# SensorPower.net
KiCad netlist of a schematic drawn in Altium Designer
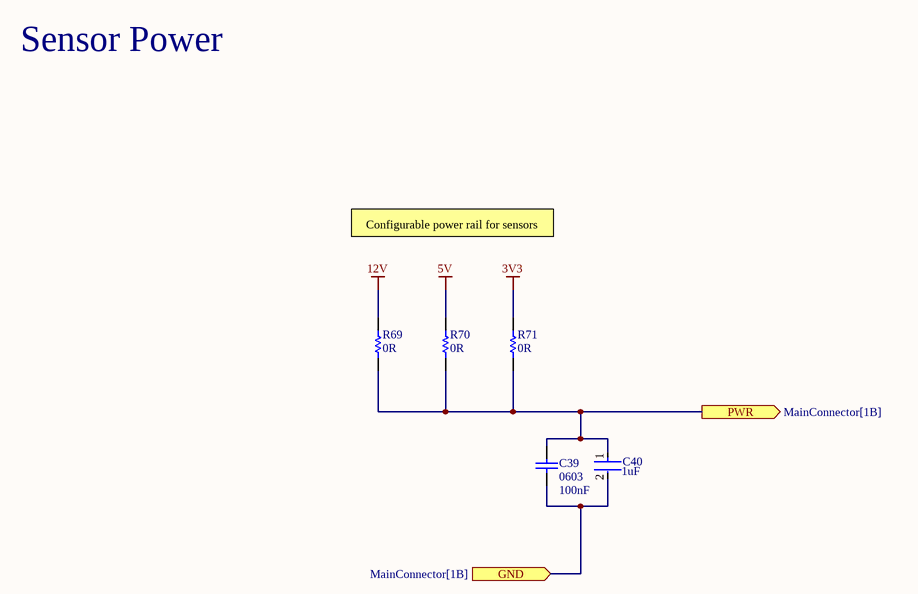
[diagram p0: SensorPower.SchDoc]

(export (version "E")
  (design (tool "Eeschema 10.0.6"))
  (components
    (comp (ref "C39")
      (value "C0603X104K5RACTU")
      (footprint "CAPC1608X87X35NL15T15")
      (fields
        (field (name "MANUFACTURER") "Kemet")
        (field (name "CASE CODE (IMPERIAL)") "0603")
        (field (name "CAPACITANCE") "100nF")
        (field (name "TOLERANCE") "10%")
        (field (name "VOLTAGE") "50V")
      )
      (libsource (lib "Altium Content Vault") (part "CAP"))
    )
    (comp (ref "C40")
      (value "CL10A105KA8NNNC")
      (footprint "FP-CL10-IPC_C")
      (description "Cap Ceramic 1uF 25V X5R ±10% Pad SMD 0603 +85°C T/R")
      (fields
        (field (name "CAPACITANCE") "1uF")
        (field (name "VOLTAGE") "25V")
        (field (name "TOLERANCE") "10%")
      )
      (libsource (lib "Altium Content Vault") (part "b4654b650e69147ec39a6b967a45e02"))
    )
    (comp (ref "R69")
      (value "RC0805JR-100RL")
      (footprint "RESC2013X60X35LL10T20")
      (description "Chip Resistor, 0 Ohm, +/- 5%, 125 mW, -55 to 155 degC, 0805 (2012 Metric), RoHS, Tape and Reel")
      (fields (field (name "MANUFACTURER") "Yageo") (field (name "RESISTANCE") "0R"))
      (libsource (lib "Altium Content Vault") (part "RES-2"))
    )
    (comp (ref "R70")
      (value "RC0805JR-100RL")
      (footprint "RESC2013X60X35LL10T20")
      (description "Chip Resistor, 0 Ohm, +/- 5%, 125 mW, -55 to 155 degC, 0805 (2012 Metric), RoHS, Tape and Reel")
      (fields (field (name "MANUFACTURER") "Yageo") (field (name "RESISTANCE") "0R"))
      (libsource (lib "Altium Content Vault") (part "RES-2"))
    )
    (comp (ref "R71")
      (value "RC0805JR-100RL")
      (footprint "RESC2013X60X35LL10T20")
      (description "Chip Resistor, 0 Ohm, +/- 5%, 125 mW, -55 to 155 degC, 0805 (2012 Metric), RoHS, Tape and Reel")
      (fields (field (name "MANUFACTURER") "Yageo") (field (name "RESISTANCE") "0R"))
      (libsource (lib "Altium Content Vault") (part "RES-2"))
    )
  )
  (nets
    (net (code "1") (name "/GND") (class "Default")
      (node (ref "C39") (pin "2") (pinfunction "2_2") (pintype "passive"))
      (node (ref "C40") (pin "2") (pinfunction "2_2") (pintype "passive"))
    )
    (net (code "2") (name "/PWR") (class "Default")
      (node (ref "C39") (pin "1") (pinfunction "1_1") (pintype "passive"))
      (node (ref "C40") (pin "1") (pinfunction "1_1") (pintype "passive"))
      (node (ref "R69") (pin "2") (pinfunction "2_2") (pintype "passive"))
      (node (ref "R70") (pin "2") (pinfunction "2_2") (pintype "passive"))
      (node (ref "R71") (pin "2") (pinfunction "2_2") (pintype "passive"))
    )
    (net (code "3") (name "3V3") (class "Default")
      (node (ref "R71") (pin "1") (pinfunction "1_1") (pintype "passive"))
    )
    (net (code "4") (name "5V") (class "Default")
      (node (ref "R70") (pin "1") (pinfunction "1_1") (pintype "passive"))
    )
    (net (code "5") (name "12V") (class "Default")
      (node (ref "R69") (pin "1") (pinfunction "1_1") (pintype "passive"))
    )
  )
)
